# TinyFaceWatch.net
KiCad netlist of a schematic drawn in EAGLE
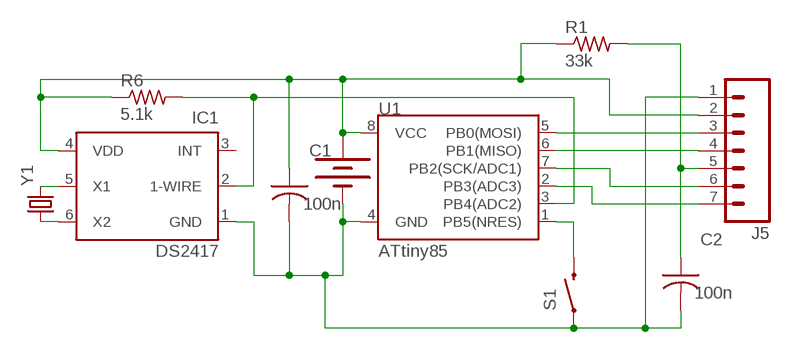
[diagram p0: schematic, sheet 1]

(export (version "E")
  (design (tool "Eeschema 10.0.6"))
  (components
    (comp (ref "BAT1")
      (value "20mm coincell")
      (footprint "eagle-import:BATTCON_20MM_4LEGS")
      (libsource (lib "eagle-import") (part "BATTERY20MM_4LEGS"))
    )
    (comp (ref "C1")
      (value "100n")
      (footprint "eagle-import:C0805K")
      (libsource (lib "eagle-import") (part "C-USC0805K"))
    )
    (comp (ref "C2")
      (value "100n")
      (footprint "eagle-import:C0805K")
      (libsource (lib "eagle-import") (part "C-USC0805K"))
    )
    (comp (ref "IC1")
      (value "DS2417")
      (footprint "eagle-import:TSOC6")
      (libsource (lib "eagle-import") (part "DS2417P"))
    )
    (comp (ref "J5")
      (value "M07")
      (footprint "eagle-import:1X07")
      (libsource (lib "eagle-import") (part "M07"))
    )
    (comp (ref "R1")
      (value "33k")
      (footprint "eagle-import:M0805")
      (libsource (lib "eagle-import") (part "R-US_M0805"))
    )
    (comp (ref "R6")
      (value "5.1k")
      (footprint "eagle-import:M0805")
      (libsource (lib "eagle-import") (part "R-US_M0805"))
    )
    (comp (ref "S1")
      (value "SWITCH-MOMENTARY-2SMD-4.6X2.8MM")
      (footprint "eagle-import:TACTILE_SWITCH_SMD_4.6X2.8MM")
      (libsource (lib "eagle-import") (part "SWITCH-MOMENTARY-2SMD-4.6X2.8MM"))
    )
    (comp (ref "U1")
      (value "ATtiny85")
      (footprint "eagle-import:SO08-EIAJ")
      (libsource (lib "eagle-import") (part "ATTINY45TINY45-20-SMT"))
    )
    (comp (ref "Y1")
      (value "CRYSTAL32-SMD-MELF")
      (footprint "eagle-import:CRYSTAL-32KHZ-SMD-MELF")
      (libsource (lib "eagle-import") (part "CRYSTAL32-SMD-MELF"))
    )
  )
  (nets
    (net (code "1") (name "/INT") (class "Default")
      (node (ref "IC1") (pin "3") (pinfunction "INT_3") (pintype "power_in"))
    )
    (net (code "2") (name "Net-(BAT1--)") (class "Default")
      (node (ref "BAT1") (pin "NEGATIVE") (pinfunction "-_NEGATIVE") (pintype "power_in"))
      (node (ref "C1") (pin "2") (pinfunction "2_2") (pintype "passive"))
      (node (ref "C2") (pin "2") (pinfunction "2_2") (pintype "passive"))
      (node (ref "IC1") (pin "1") (pinfunction "GND_1") (pintype "power_in"))
      (node (ref "J5") (pin "1") (pinfunction "1_1") (pintype "passive"))
      (node (ref "S1") (pin "1") (pinfunction "1_1") (pintype "passive"))
      (node (ref "S1") (pin "2") (pinfunction "1_2") (pintype "passive"))
      (node (ref "U1") (pin "4") (pinfunction "GND_4") (pintype "bidirectional"))
    )
    (net (code "3") (name "Net-(C2-Pad1)") (class "Default")
      (node (ref "C2") (pin "1") (pinfunction "1_1") (pintype "passive"))
      (node (ref "J5") (pin "5") (pinfunction "5_5") (pintype "passive"))
      (node (ref "R1") (pin "2") (pinfunction "2_2") (pintype "passive"))
    )
    (net (code "4") (name "Net-(IC1-1-WIRE)") (class "Default")
      (node (ref "IC1") (pin "2") (pinfunction "1-WIRE_2") (pintype "bidirectional"))
      (node (ref "R6") (pin "2") (pinfunction "2_2") (pintype "passive"))
      (node (ref "U1") (pin "3") (pinfunction "PB4(ADC2)_3") (pintype "bidirectional"))
    )
    (net (code "5") (name "Net-(IC1-VDD)") (class "Default")
      (node (ref "BAT1") (pin "POSITIVE@1") (pinfunction "+_POSITIVE@1") (pintype "power_in"))
      (node (ref "BAT1") (pin "POSITIVE@2") (pinfunction "+_POSITIVE@2") (pintype "power_in"))
      (node (ref "BAT1") (pin "POSITIVE@3") (pinfunction "+_POSITIVE@3") (pintype "power_in"))
      (node (ref "BAT1") (pin "POSITIVE@4") (pinfunction "+_POSITIVE@4") (pintype "power_in"))
      (node (ref "C1") (pin "1") (pinfunction "1_1") (pintype "passive"))
      (node (ref "IC1") (pin "4") (pinfunction "VDD_4") (pintype "passive"))
      (node (ref "J5") (pin "2") (pinfunction "2_2") (pintype "passive"))
      (node (ref "R1") (pin "1") (pinfunction "1_1") (pintype "passive"))
      (node (ref "R6") (pin "1") (pinfunction "1_1") (pintype "passive"))
      (node (ref "U1") (pin "8") (pinfunction "VCC_8") (pintype "bidirectional"))
    )
    (net (code "6") (name "Net-(IC1-X1)") (class "Default")
      (node (ref "IC1") (pin "5") (pinfunction "X1_5") (pintype "passive"))
      (node (ref "Y1") (pin "X2") (pinfunction "2_X2") (pintype "passive"))
    )
    (net (code "7") (name "Net-(IC1-X2)") (class "Default")
      (node (ref "IC1") (pin "6") (pinfunction "X2_6") (pintype "passive"))
      (node (ref "Y1") (pin "X1") (pinfunction "1_X1") (pintype "passive"))
    )
    (net (code "8") (name "Net-(U1-PB0(MOSI))") (class "Default")
      (node (ref "J5") (pin "3") (pinfunction "3_3") (pintype "passive"))
      (node (ref "U1") (pin "5") (pinfunction "PB0(MOSI)_5") (pintype "bidirectional"))
    )
    (net (code "9") (name "Net-(U1-PB1(MISO))") (class "Default")
      (node (ref "J5") (pin "4") (pinfunction "4_4") (pintype "passive"))
      (node (ref "U1") (pin "6") (pinfunction "PB1(MISO)_6") (pintype "bidirectional"))
    )
    (net (code "10") (name "Net-(U1-PB2(SCK{slash}ADC1))") (class "Default")
      (node (ref "J5") (pin "6") (pinfunction "6_6") (pintype "passive"))
      (node (ref "U1") (pin "7") (pinfunction "PB2(SCK/ADC1)_7") (pintype "bidirectional"))
    )
    (net (code "11") (name "Net-(U1-PB3(ADC3))") (class "Default")
      (node (ref "J5") (pin "7") (pinfunction "7_7") (pintype "passive"))
      (node (ref "U1") (pin "2") (pinfunction "PB3(ADC3)_2") (pintype "bidirectional"))
    )
    (net (code "12") (name "Net-(U1-PB5(NRES))") (class "Default")
      (node (ref "S1") (pin "3") (pinfunction "2_3") (pintype "passive"))
      (node (ref "S1") (pin "4") (pinfunction "2_4") (pintype "passive"))
      (node (ref "U1") (pin "1") (pinfunction "PB5(NRES)_1") (pintype "bidirectional"))
    )
  )
)
